# Codec.net
KiCad netlist of a schematic drawn in Altium Designer
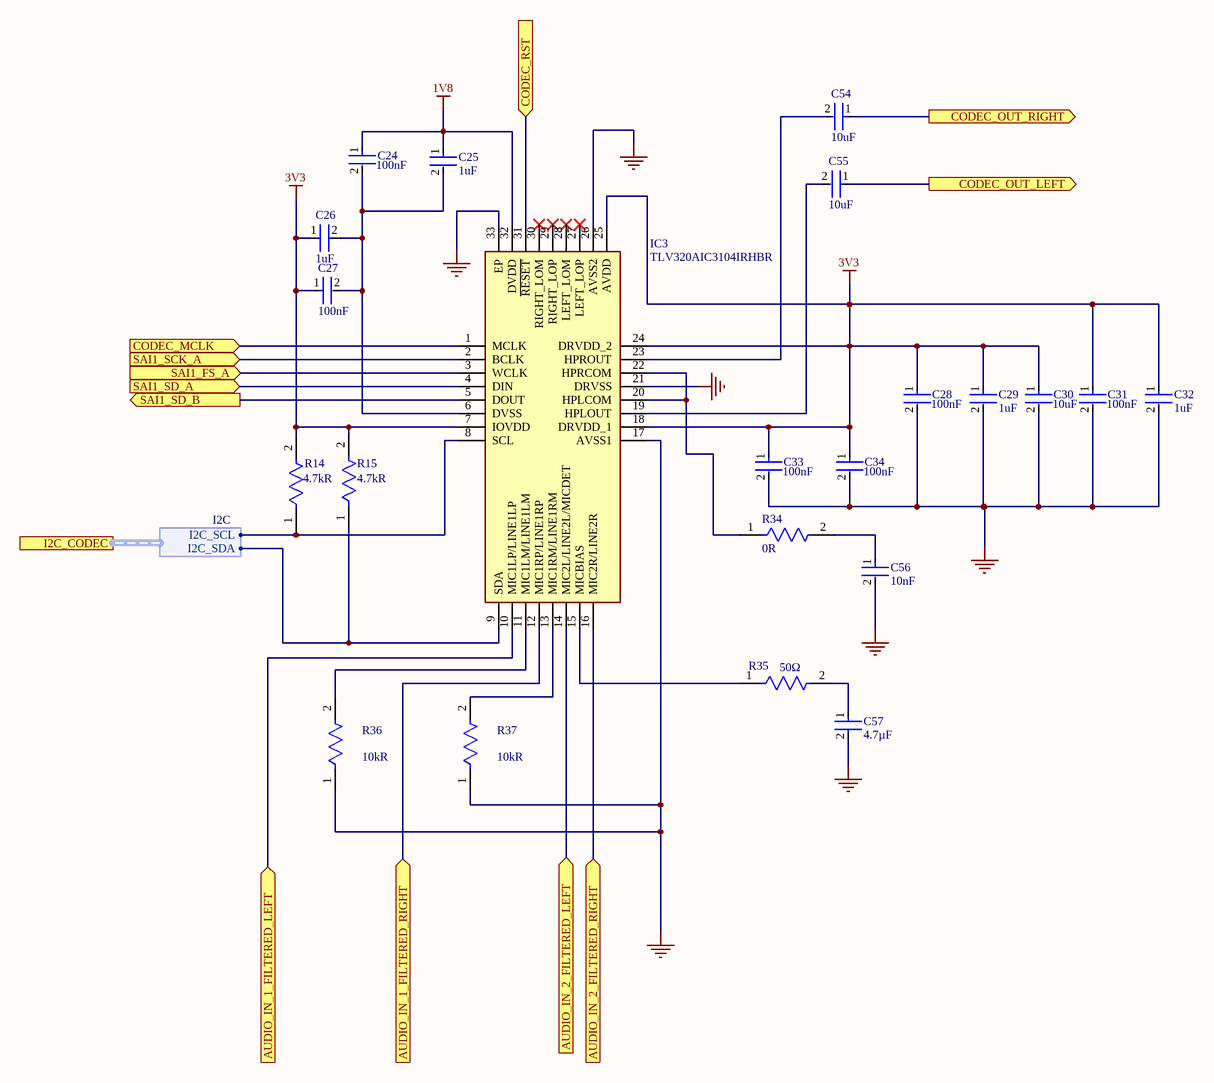
[diagram p0: Codec.SchDoc]

(export (version "E")
  (design (tool "Eeschema 10.0.6"))
  (components
    (comp (ref "C24")
      (value "GRM033C71C104ME14J")
      (footprint "FP-GRM033-0_03-IPC_C")
      (description "Chip Multilayer Ceramic Capacitors for General Purpose, 0201, 0.10uF, X7S, 22%, 20%, 16V")
      (fields (field (name "TOLERANCE") "20%") (field (name "CAPACITANCE") "100nF"))
      (libsource (lib "Altium Content Vault") (part "b4654b650e69147ec39a6b967a45e02"))
    )
    (comp (ref "C25")
      (value "GRM155C70J105ME11J")
      (footprint "FP-GRM155-0_1-IPC_B")
      (description "Chip Multilayer Ceramic Capacitors for General Purpose, 0402, 1.0uF, X7S, 22%, 20%, 6.3V")
      (fields (field (name "TOLERANCE") "20%") (field (name "CAPACITANCE") "1uF"))
      (libsource (lib "Altium Content Vault") (part "11868f565c42a9108669ba33697ecf6"))
    )
    (comp (ref "C26")
      (value "GRM155C70J105ME11J")
      (footprint "FP-GRM155-0_1-IPC_B")
      (description "Chip Multilayer Ceramic Capacitors for General Purpose, 0402, 1.0uF, X7S, 22%, 20%, 6.3V")
      (fields (field (name "TOLERANCE") "20%") (field (name "CAPACITANCE") "1uF"))
      (libsource (lib "Altium Content Vault") (part "11868f565c42a9108669ba33697ecf6"))
    )
    (comp (ref "C27")
      (value "GRM033C71C104ME14J")
      (footprint "FP-GRM033-0_03-IPC_C")
      (description "Chip Multilayer Ceramic Capacitors for General Purpose, 0201, 0.10uF, X7S, 22%, 20%, 16V")
      (fields (field (name "TOLERANCE") "20%") (field (name "CAPACITANCE") "100nF"))
      (libsource (lib "Altium Content Vault") (part "b4654b650e69147ec39a6b967a45e02"))
    )
    (comp (ref "C28")
      (value "GRM033C71C104ME14J")
      (footprint "FP-GRM033-0_03-IPC_C")
      (description "Chip Multilayer Ceramic Capacitors for General Purpose, 0201, 0.10uF, X7S, 22%, 20%, 16V")
      (fields (field (name "TOLERANCE") "20%") (field (name "CAPACITANCE") "100nF"))
      (libsource (lib "Altium Content Vault") (part "b4654b650e69147ec39a6b967a45e02"))
    )
    (comp (ref "C29")
      (value "GRM155C70J105ME11J")
      (footprint "FP-GRM155-0_1-IPC_B")
      (description "Chip Multilayer Ceramic Capacitors for General Purpose, 0402, 1.0uF, X7S, 22%, 20%, 6.3V")
      (fields (field (name "TOLERANCE") "20%") (field (name "CAPACITANCE") "1uF"))
      (libsource (lib "Altium Content Vault") (part "11868f565c42a9108669ba33697ecf6"))
    )
    (comp (ref "C30")
      (value "GRM21BC81E106KE51K")
      (footprint "FP-GRM21B-0_15-IPC_C")
      (description "Chip Multilayer Ceramic Capacitors for General Purpose, 0805, 10uF, X6S, 22%, 10%, 25V")
      (fields (field (name "CAPACITANCE") "10uF") (field (name "TOLERANCE") "10%"))
      (libsource (lib "Altium Content Vault") (part "b4654b650e69147ec39a6b967a45e02"))
    )
    (comp (ref "C31")
      (value "GRM033C71C104ME14J")
      (footprint "FP-GRM033-0_03-IPC_C")
      (description "Chip Multilayer Ceramic Capacitors for General Purpose, 0201, 0.10uF, X7S, 22%, 20%, 16V")
      (fields (field (name "TOLERANCE") "20%") (field (name "CAPACITANCE") "100nF"))
      (libsource (lib "Altium Content Vault") (part "b4654b650e69147ec39a6b967a45e02"))
    )
    (comp (ref "C32")
      (value "GRM155C70J105ME11J")
      (footprint "FP-GRM155-0_1-IPC_B")
      (description "Chip Multilayer Ceramic Capacitors for General Purpose, 0402, 1.0uF, X7S, 22%, 20%, 6.3V")
      (fields (field (name "TOLERANCE") "20%") (field (name "CAPACITANCE") "1uF"))
      (libsource (lib "Altium Content Vault") (part "11868f565c42a9108669ba33697ecf6"))
    )
    (comp (ref "C33")
      (value "GRM033C71C104ME14J")
      (footprint "FP-GRM033-0_03-IPC_C")
      (description "Chip Multilayer Ceramic Capacitors for General Purpose, 0201, 0.10uF, X7S, 22%, 20%, 16V")
      (fields (field (name "TOLERANCE") "20%") (field (name "CAPACITANCE") "100nF"))
      (libsource (lib "Altium Content Vault") (part "b4654b650e69147ec39a6b967a45e02"))
    )
    (comp (ref "C34")
      (value "GRM033C71C104ME14J")
      (footprint "FP-GRM033-0_03-IPC_C")
      (description "Chip Multilayer Ceramic Capacitors for General Purpose, 0201, 0.10uF, X7S, 22%, 20%, 16V")
      (fields (field (name "TOLERANCE") "20%") (field (name "CAPACITANCE") "100nF"))
      (libsource (lib "Altium Content Vault") (part "b4654b650e69147ec39a6b967a45e02"))
    )
    (comp (ref "C54")
      (value "GRM21BC81E106KE51K")
      (footprint "FP-GRM21B-0_15-IPC_C")
      (description "Chip Multilayer Ceramic Capacitors for General Purpose, 0805, 10uF, X6S, 22%, 10%, 25V")
      (fields (field (name "CAPACITANCE") "10uF") (field (name "TOLERANCE") "10%"))
      (libsource (lib "Altium Content Vault") (part "b4654b650e69147ec39a6b967a45e02"))
    )
    (comp (ref "C55")
      (value "GRM21BC81E106KE51K")
      (footprint "FP-GRM21B-0_15-IPC_C")
      (description "Chip Multilayer Ceramic Capacitors for General Purpose, 0805, 10uF, X6S, 22%, 10%, 25V")
      (fields (field (name "CAPACITANCE") "10uF") (field (name "TOLERANCE") "10%"))
      (libsource (lib "Altium Content Vault") (part "b4654b650e69147ec39a6b967a45e02"))
    )
    (comp (ref "C56")
      (value "GCM155R71H103KA55W")
      (footprint "FP-GCM155-0_05-MFG")
      (description "Ceramic Capacitor for Automotive 10nF ±10% 50VDC X7R 0402 Paper T/R")
      (fields (field (name "CAPACITANCE") "10nF"))
      (libsource (lib "Altium Content Vault") (part "02cd4be3c70576c341d710602a673aa"))
    )
    (comp (ref "C57")
      (value "GCM155D70G475ME36D")
      (footprint "FP-GCM155-0_2-MFG")
      (description "GCM155D70G475ME36D AC 2C 216S Skt Recp")
      (fields (field (name "TOLERANCE") "20%") (field (name "CAPACITANCE") "4.7µF"))
      (libsource (lib "Altium Content Vault") (part "b4654b650e69147ec39a6b967a45e02"))
    )
    (comp (ref "IC3")
      (value "TLV320AIC3104IRHBR")
      (footprint "TLV320AIC3104IRHBR")
      (description "Integrated Circuit")
      (fields (field (name "MOUSER PART NUMBER") "595-TLV320C3104IRHBR"))
      (libsource (lib "audio_dev_pcb") (part "TLV320AIC3104IRHBR"))
    )
    (comp (ref "R14")
      (value "RC1005J472CS")
      (footprint "FP-RC1005-IPC_C")
      (description "Res Thick Film 0402 4.7kΩ 5% 0.063W ±100ppm/°C Molded SMD T/R")
      (fields (field (name "RESISTANCE") "4.7kR") (field (name "TOLERANCE") "5%"))
      (libsource (lib "Altium Content Vault") (part "1029c3af85768c4190bb7ad29bc67b5"))
    )
    (comp (ref "R15")
      (value "RC1005J472CS")
      (footprint "FP-RC1005-IPC_C")
      (description "Res Thick Film 0402 4.7kΩ 5% 0.063W ±100ppm/°C Molded SMD T/R")
      (fields (field (name "RESISTANCE") "4.7kR") (field (name "TOLERANCE") "5%"))
      (libsource (lib "Altium Content Vault") (part "1029c3af85768c4190bb7ad29bc67b5"))
    )
    (comp (ref "R34")
      (value "RMCF0402ZT0R00")
      (footprint "FP-RMCF0402-MFG")
      (description "RES 0 OHM JUMPER 1/16W 0402")
      (fields (field (name "RESISTANCE") "0R"))
      (libsource (lib "Altium Content Vault") (part "1029c3af85768c4190bb7ad29bc67b5"))
    )
    (comp (ref "R35")
      (value "RC0402JR-0750RL")
      (footprint "FP-RC0402-0_4-MFG")
      (fields (field (name "RESISTANCE") "50Ω") (field (name "TOLERANCE") "5%"))
      (libsource (lib "Altium Content Vault") (part "1029c3af85768c4190bb7ad29bc67b5"))
    )
    (comp (ref "R36")
      (value "RC0402FR-1310KL")
      (footprint "FP-RC0402-0_4-IPC_A")
      (description "RESISTOR 0402 10K 1%")
      (fields (field (name "RESISTANCE") "10kR") (field (name "TOLERANCE") "1%"))
      (libsource (lib "Altium Content Vault") (part "1029c3af85768c4190bb7ad29bc67b5"))
    )
    (comp (ref "R37")
      (value "RC0402FR-1310KL")
      (footprint "FP-RC0402-0_4-IPC_A")
      (description "RESISTOR 0402 10K 1%")
      (fields (field (name "RESISTANCE") "10kR") (field (name "TOLERANCE") "1%"))
      (libsource (lib "Altium Content Vault") (part "1029c3af85768c4190bb7ad29bc67b5"))
    )
  )
  (nets
    (net (code "2") (name "/AUDIO_IN_1_FILTERED_LEFT") (class "Default")
      (node (ref "IC3") (pin "10") (pinfunction "MIC1LP/LINE1LP_10") (pintype "passive"))
    )
    (net (code "3") (name "/AUDIO_IN_1_FILTERED_RIGHT") (class "Default")
      (node (ref "IC3") (pin "12") (pinfunction "MIC1RP/LINE1RP_12") (pintype "passive"))
    )
    (net (code "4") (name "/AUDIO_IN_2_FILTERED_LEFT") (class "Default")
      (node (ref "IC3") (pin "14") (pinfunction "MIC2L/LINE2L/MICDET_14") (pintype "passive"))
    )
    (net (code "5") (name "/AUDIO_IN_2_FILTERED_RIGHT") (class "Default")
      (node (ref "IC3") (pin "16") (pinfunction "MIC2R/LINE2R_16") (pintype "passive"))
    )
    (net (code "6") (name "/CODEC_MCLK") (class "Default")
      (node (ref "IC3") (pin "1") (pinfunction "MCLK_1") (pintype "passive"))
    )
    (net (code "7") (name "/CODEC_OUT_LEFT") (class "Default")
      (node (ref "C55") (pin "1") (pinfunction "1_1") (pintype "passive"))
    )
    (net (code "8") (name "/CODEC_OUT_RIGHT") (class "Default")
      (node (ref "C54") (pin "1") (pinfunction "1_1") (pintype "passive"))
    )
    (net (code "9") (name "/CODEC_RST") (class "Default")
      (node (ref "IC3") (pin "31") (pinfunction "~{RESET}_31") (pintype "passive"))
    )
    (net (code "10") (name "/SAI1_FS_A") (class "Default")
      (node (ref "IC3") (pin "3") (pinfunction "WCLK_3") (pintype "passive"))
    )
    (net (code "11") (name "/SAI1_SCK_A") (class "Default")
      (node (ref "IC3") (pin "2") (pinfunction "BCLK_2") (pintype "passive"))
    )
    (net (code "12") (name "/SAI1_SD_A") (class "Default")
      (node (ref "IC3") (pin "4") (pinfunction "DIN_4") (pintype "passive"))
    )
    (net (code "13") (name "/SAI1_SD_B") (class "Default")
      (node (ref "IC3") (pin "5") (pinfunction "DOUT_5") (pintype "passive"))
    )
    (net (code "15") (name "1V8") (class "Default")
      (node (ref "C24") (pin "1") (pinfunction "1_1") (pintype "passive"))
      (node (ref "C25") (pin "1") (pinfunction "1_1") (pintype "passive"))
      (node (ref "IC3") (pin "32") (pinfunction "DVDD_32") (pintype "passive"))
    )
    (net (code "16") (name "3V3") (class "Default")
      (node (ref "C26") (pin "1") (pinfunction "1_1") (pintype "passive"))
      (node (ref "C27") (pin "1") (pinfunction "1_1") (pintype "passive"))
      (node (ref "C28") (pin "1") (pinfunction "1_1") (pintype "passive"))
      (node (ref "C29") (pin "1") (pinfunction "1_1") (pintype "passive"))
      (node (ref "C30") (pin "1") (pinfunction "1_1") (pintype "passive"))
      (node (ref "C31") (pin "1") (pinfunction "1_1") (pintype "passive"))
      (node (ref "C32") (pin "1") (pinfunction "1_1") (pintype "passive"))
      (node (ref "C33") (pin "1") (pinfunction "1_1") (pintype "passive"))
      (node (ref "C34") (pin "1") (pinfunction "1_1") (pintype "passive"))
      (node (ref "IC3") (pin "18") (pinfunction "DRVDD_1_18") (pintype "passive"))
      (node (ref "IC3") (pin "24") (pinfunction "DRVDD_2_24") (pintype "passive"))
      (node (ref "IC3") (pin "25") (pinfunction "AVDD_25") (pintype "passive"))
      (node (ref "IC3") (pin "7") (pinfunction "IOVDD_7") (pintype "passive"))
      (node (ref "R14") (pin "2") (pinfunction "2_2") (pintype "passive"))
      (node (ref "R15") (pin "2") (pinfunction "2_2") (pintype "passive"))
    )
    (net (code "17") (name "GND") (class "Default")
      (node (ref "C28") (pin "2") (pinfunction "2_2") (pintype "passive"))
      (node (ref "C29") (pin "2") (pinfunction "2_2") (pintype "passive"))
      (node (ref "C30") (pin "2") (pinfunction "2_2") (pintype "passive"))
      (node (ref "C31") (pin "2") (pinfunction "2_2") (pintype "passive"))
      (node (ref "C32") (pin "2") (pinfunction "2_2") (pintype "passive"))
      (node (ref "C33") (pin "2") (pinfunction "2_2") (pintype "passive"))
      (node (ref "C34") (pin "2") (pinfunction "2_2") (pintype "passive"))
      (node (ref "C56") (pin "2") (pinfunction "2_2") (pintype "passive"))
      (node (ref "C57") (pin "2") (pinfunction "2_2") (pintype "passive"))
      (node (ref "IC3") (pin "17") (pinfunction "AVSS1_17") (pintype "passive"))
      (node (ref "IC3") (pin "21") (pinfunction "DRVSS_21") (pintype "passive"))
      (node (ref "IC3") (pin "26") (pinfunction "AVSS2_26") (pintype "passive"))
      (node (ref "IC3") (pin "33") (pinfunction "EP_33") (pintype "passive"))
      (node (ref "R36") (pin "1") (pinfunction "1_1") (pintype "passive"))
      (node (ref "R37") (pin "1") (pinfunction "1_1") (pintype "passive"))
    )
    (net (code "18") (name "Net-(C56-Pad1)") (class "Default")
      (node (ref "C56") (pin "1") (pinfunction "1_1") (pintype "passive"))
      (node (ref "R34") (pin "2") (pinfunction "2_2") (pintype "passive"))
    )
    (net (code "19") (name "Net-(C57-Pad1)") (class "Default")
      (node (ref "C57") (pin "1") (pinfunction "1_1") (pintype "passive"))
      (node (ref "R35") (pin "2") (pinfunction "2_2") (pintype "passive"))
    )
    (net (code "20") (name "Net-(IC3-DVSS)") (class "Default")
      (node (ref "C24") (pin "2") (pinfunction "2_2") (pintype "passive"))
      (node (ref "C25") (pin "2") (pinfunction "2_2") (pintype "passive"))
      (node (ref "C26") (pin "2") (pinfunction "2_2") (pintype "passive"))
      (node (ref "C27") (pin "2") (pinfunction "2_2") (pintype "passive"))
      (node (ref "IC3") (pin "6") (pinfunction "DVSS_6") (pintype "passive"))
    )
    (net (code "21") (name "Net-(IC3-HPLCOM)") (class "Default")
      (node (ref "IC3") (pin "20") (pinfunction "HPLCOM_20") (pintype "passive"))
      (node (ref "IC3") (pin "22") (pinfunction "HPRCOM_22") (pintype "passive"))
      (node (ref "R34") (pin "1") (pinfunction "1_1") (pintype "passive"))
    )
    (net (code "22") (name "Net-(IC3-HPLOUT)") (class "Default")
      (node (ref "C55") (pin "2") (pinfunction "2_2") (pintype "passive"))
      (node (ref "IC3") (pin "19") (pinfunction "HPLOUT_19") (pintype "passive"))
    )
    (net (code "23") (name "Net-(IC3-HPROUT)") (class "Default")
      (node (ref "C54") (pin "2") (pinfunction "2_2") (pintype "passive"))
      (node (ref "IC3") (pin "23") (pinfunction "HPROUT_23") (pintype "passive"))
    )
    (net (code "24") (name "Net-(IC3-MIC1LM{slash}LINE1LM)") (class "Default")
      (node (ref "IC3") (pin "11") (pinfunction "MIC1LM/LINE1LM_11") (pintype "passive"))
      (node (ref "R36") (pin "2") (pinfunction "2_2") (pintype "passive"))
    )
    (net (code "25") (name "Net-(IC3-MIC1RM{slash}LINE1RM)") (class "Default")
      (node (ref "IC3") (pin "13") (pinfunction "MIC1RM/LINE1RM_13") (pintype "passive"))
      (node (ref "R37") (pin "2") (pinfunction "2_2") (pintype "passive"))
    )
    (net (code "26") (name "Net-(IC3-MICBIAS)") (class "Default")
      (node (ref "IC3") (pin "15") (pinfunction "MICBIAS_15") (pintype "passive"))
      (node (ref "R35") (pin "1") (pinfunction "1_1") (pintype "passive"))
    )
    (net (code "27") (name "Net-(IC3-SCL)") (class "Default")
      (node (ref "IC3") (pin "8") (pinfunction "SCL_8") (pintype "passive"))
      (node (ref "R14") (pin "1") (pinfunction "1_1") (pintype "passive"))
    )
    (net (code "28") (name "Net-(IC3-SDA)") (class "Default")
      (node (ref "IC3") (pin "9") (pinfunction "SDA_9") (pintype "passive"))
      (node (ref "R15") (pin "1") (pinfunction "1_1") (pintype "passive"))
    )
    (net (code "29") (name "unconnected-(IC3-LEFT_LOM-Pad28)") (class "Default")
      (node (ref "IC3") (pin "28") (pinfunction "LEFT_LOM_28") (pintype "passive+no_connect"))
    )
    (net (code "30") (name "unconnected-(IC3-LEFT_LOP-Pad27)") (class "Default")
      (node (ref "IC3") (pin "27") (pinfunction "LEFT_LOP_27") (pintype "passive+no_connect"))
    )
    (net (code "31") (name "unconnected-(IC3-RIGHT_LOM-Pad30)") (class "Default")
      (node (ref "IC3") (pin "30") (pinfunction "RIGHT_LOM_30") (pintype "passive+no_connect"))
    )
    (net (code "32") (name "unconnected-(IC3-RIGHT_LOP-Pad29)") (class "Default")
      (node (ref "IC3") (pin "29") (pinfunction "RIGHT_LOP_29") (pintype "passive+no_connect"))
    )
  )
)
